# Transformer_FrontEnd_2.net
KiCad netlist of a schematic drawn in Altium Designer
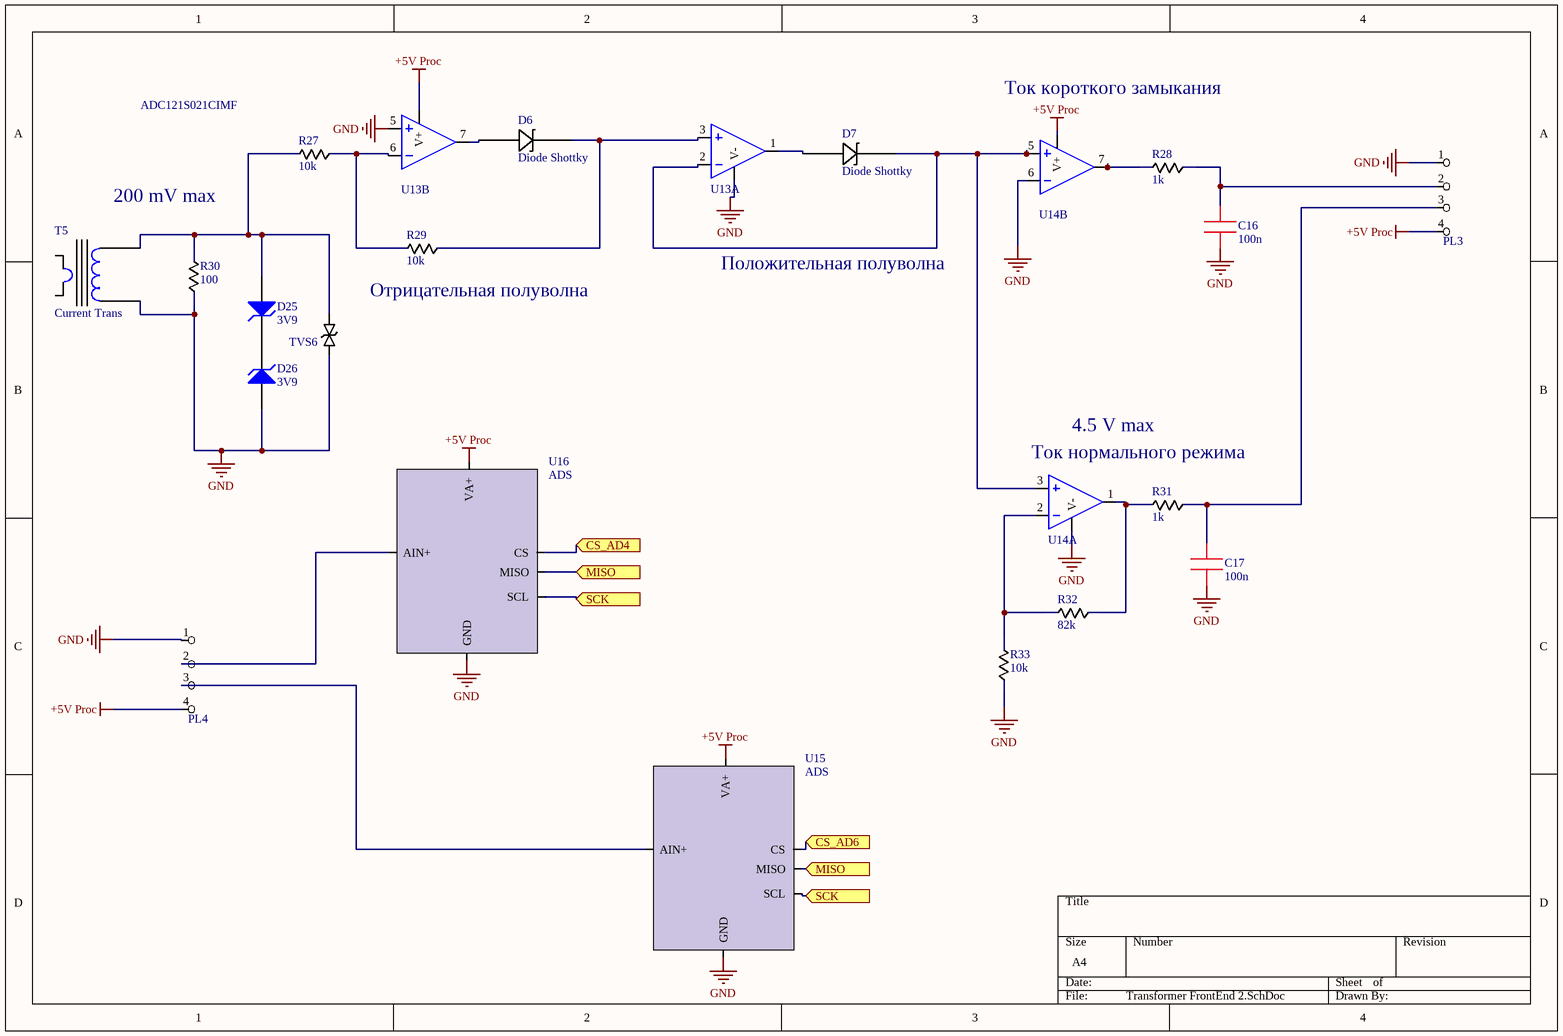
[diagram p0: Transformer FrontEnd 2.SchDoc]

(export (version "E")
  (design (tool "Eeschema 10.0.6"))
  (components
    (comp (ref "C16")
      (value "100n")
      (footprint "0603")
      (description "CC0603KRX7R9BB104")
      (libsource (lib "kontr") (part "0603 CAP"))
    )
    (comp (ref "C17")
      (value "100n")
      (footprint "0603")
      (description "CC0603KRX7R9BB104")
      (libsource (lib "kontr") (part "0603 CAP"))
    )
    (comp (ref "D6")
      (value "Diode Shottky")
      (footprint "SOD523")
      (description "RB751S40T1G")
      (libsource (lib "kontr") (part "Diode Shottky"))
    )
    (comp (ref "D7")
      (value "Diode Shottky")
      (footprint "SOD523")
      (description "RB751S40T1G")
      (libsource (lib "kontr") (part "Diode Shottky"))
    )
    (comp (ref "D25")
      (value "3V9")
      (footprint "PcbLib1:SOD80C")
      (description "BZV55-C3V9,115")
      (libsource (lib "Miscellaneous Devices") (part "D Zener"))
    )
    (comp (ref "D26")
      (value "3V9")
      (footprint "PcbLib1:SOD80C")
      (description "BZV55-C3V9,115")
      (libsource (lib "Miscellaneous Devices") (part "D Zener"))
    )
    (comp (ref "PL3")
      (value "plug")
      (footprint "PLS 4")
      (description "PLS-4R (DS1022-1x4R)")
      (libsource (lib "kontr") (part "PLS-4R"))
    )
    (comp (ref "PL4")
      (value "plug")
      (footprint "PLS 4")
      (description "PLS-4R (DS1022-1x4R)")
      (libsource (lib "kontr") (part "PLS-4R"))
    )
    (comp (ref "R27")
      (value "10k")
      (footprint "0603")
      (description "RT0603FRE0710KL")
      (libsource (lib "kontr") (part "0603 RES"))
    )
    (comp (ref "R28")
      (value "1k")
      (footprint "0603")
      (description "RC0603FR-071KL")
      (libsource (lib "kontr") (part "0603 RES"))
    )
    (comp (ref "R29")
      (value "10k")
      (footprint "0603")
      (description "RT0603FRE0710KL")
      (libsource (lib "kontr") (part "0603 RES"))
    )
    (comp (ref "R30")
      (value "100")
      (footprint "1206")
      (description "RT1206BRD07100RL")
      (libsource (lib "kontr") (part "SMD Resistor"))
    )
    (comp (ref "R31")
      (value "1k")
      (footprint "0603")
      (description "RC0603FR-071KL")
      (libsource (lib "kontr") (part "0603 RES"))
    )
    (comp (ref "R32")
      (value "82k")
      (footprint "0603")
      (description "ERJ3EKF8202V")
      (libsource (lib "kontr") (part "0603 RES"))
    )
    (comp (ref "R33")
      (value "10k")
      (footprint "0603")
      (description "RT0603FRE0710KL")
      (libsource (lib "kontr") (part "0603 RES"))
    )
    (comp (ref "T5")
      (value "Current Trans")
      (footprint "Talema")
      (description "AC-1005")
      (libsource (lib "kontr") (part "Current Trans"))
    )
    (comp (ref "TVS6")
      (value "SMAJ5.0CA")
      (footprint "DO-214AC")
      (libsource (lib "kontr") (part "SMAJ5.0CA"))
    )
    (comp (ref "U13")
      (value "OPAMP 2Ch")
      (footprint "SOIC 8")
      (description "TS272IDT")
      (libsource (lib "kontr") (part "OPAMP 2Ch"))
    )
    (comp (ref "U14")
      (value "OPAMP 2Ch")
      (footprint "SOIC 8")
      (description "TS272IDT")
      (libsource (lib "kontr") (part "OPAMP 2Ch"))
    )
    (comp (ref "U15")
      (value "ADS")
      (footprint "SOT23 - 6")
      (description "ADC121S021CIMF")
      (libsource (lib "kontr") (part "ADS"))
    )
    (comp (ref "U16")
      (value "ADS")
      (footprint "SOT23 - 6")
      (description "ADC121S021CIMF")
      (libsource (lib "kontr") (part "ADS"))
    )
  )
  (nets
    (net (code "1") (name "+5V Proc") (class "Default")
      (node (ref "PL3") (pin "4") (pinfunction "2_4") (pintype "passive"))
      (node (ref "PL4") (pin "4") (pinfunction "2_4") (pintype "passive"))
      (node (ref "U13") (pin "8") (pinfunction "V+_8") (pintype "passive"))
      (node (ref "U14") (pin "8") (pinfunction "V+_8") (pintype "passive"))
      (node (ref "U15") (pin "1") (pinfunction "VA+_1") (pintype "passive"))
      (node (ref "U16") (pin "1") (pinfunction "VA+_1") (pintype "passive"))
    )
    (net (code "2") (name "/CS_AD4") (class "Default")
      (node (ref "U16") (pin "6") (pinfunction "CS_6") (pintype "passive"))
    )
    (net (code "3") (name "/CS_AD6") (class "Default")
      (node (ref "U15") (pin "6") (pinfunction "CS_6") (pintype "passive"))
    )
    (net (code "4") (name "/MISO") (class "Default")
      (node (ref "U15") (pin "5") (pinfunction "MISO_5") (pintype "passive"))
      (node (ref "U16") (pin "5") (pinfunction "MISO_5") (pintype "passive"))
    )
    (net (code "5") (name "/SCK") (class "Default")
      (node (ref "U15") (pin "4") (pinfunction "SCL_4") (pintype "passive"))
      (node (ref "U16") (pin "4") (pinfunction "SCL_4") (pintype "passive"))
    )
    (net (code "6") (name "GND") (class "Default")
      (node (ref "C16") (pin "1") (pinfunction "1_1") (pintype "passive"))
      (node (ref "C17") (pin "1") (pinfunction "1_1") (pintype "passive"))
      (node (ref "D26") (pin "1") (pinfunction "A_1") (pintype "passive"))
      (node (ref "PL3") (pin "1") (pinfunction "1_1") (pintype "passive"))
      (node (ref "PL4") (pin "1") (pinfunction "1_1") (pintype "passive"))
      (node (ref "R30") (pin "1") (pintype "passive"))
      (node (ref "R33") (pin "1") (pintype "passive"))
      (node (ref "T5") (pin "2") (pinfunction "2_2") (pintype "passive"))
      (node (ref "TVS6") (pin "1") (pinfunction "1_1") (pintype "passive"))
      (node (ref "U13") (pin "4") (pinfunction "V-_4") (pintype "passive"))
      (node (ref "U13") (pin "5") (pinfunction "+IN_5") (pintype "passive"))
      (node (ref "U14") (pin "4") (pinfunction "V-_4") (pintype "passive"))
      (node (ref "U14") (pin "6") (pinfunction "-IN_6") (pintype "passive"))
      (node (ref "U15") (pin "2") (pinfunction "GND_2") (pintype "passive"))
      (node (ref "U16") (pin "2") (pinfunction "GND_2") (pintype "passive"))
    )
    (net (code "7") (name "Net-(C16-Pad2)") (class "Default")
      (node (ref "C16") (pin "2") (pinfunction "2_2") (pintype "passive"))
      (node (ref "PL3") (pin "2") (pinfunction "2_2") (pintype "passive"))
      (node (ref "R28") (pin "1") (pintype "passive"))
    )
    (net (code "8") (name "Net-(C17-Pad2)") (class "Default")
      (node (ref "C17") (pin "2") (pinfunction "2_2") (pintype "passive"))
      (node (ref "PL3") (pin "3") (pinfunction "1_3") (pintype "passive"))
      (node (ref "R31") (pin "1") (pintype "passive"))
    )
    (net (code "9") (name "Net-(D25-A)") (class "Default")
      (node (ref "D25") (pin "1") (pinfunction "A_1") (pintype "passive"))
      (node (ref "R27") (pin "2") (pintype "passive"))
      (node (ref "R30") (pin "2") (pintype "passive"))
      (node (ref "T5") (pin "1") (pinfunction "1_1") (pintype "passive"))
      (node (ref "TVS6") (pin "2") (pinfunction "2_2") (pintype "passive"))
    )
    (net (code "10") (name "Net-(D25-K)") (class "Default")
      (node (ref "D25") (pin "2") (pinfunction "K_2") (pintype "passive"))
      (node (ref "D26") (pin "2") (pinfunction "K_2") (pintype "passive"))
    )
    (net (code "11") (name "Net-(U13A-+IN)") (class "Default")
      (node (ref "D6") (pin "2") (pinfunction "2_2") (pintype "passive"))
      (node (ref "R29") (pin "1") (pintype "passive"))
      (node (ref "U13") (pin "3") (pinfunction "+IN_3") (pintype "passive"))
    )
    (net (code "12") (name "Net-(U13A--IN)") (class "Default")
      (node (ref "D7") (pin "2") (pinfunction "2_2") (pintype "passive"))
      (node (ref "U13") (pin "2") (pinfunction "-IN_2") (pintype "passive"))
      (node (ref "U14") (pin "3") (pinfunction "+IN_3") (pintype "passive"))
      (node (ref "U14") (pin "5") (pinfunction "+IN_5") (pintype "passive"))
    )
    (net (code "13") (name "Net-(U13A-OUT)") (class "Default")
      (node (ref "D7") (pin "1") (pinfunction "1_1") (pintype "passive"))
      (node (ref "U13") (pin "1") (pinfunction "OUT_1") (pintype "passive"))
    )
    (net (code "14") (name "Net-(U13B--IN)") (class "Default")
      (node (ref "R27") (pin "1") (pintype "passive"))
      (node (ref "R29") (pin "2") (pintype "passive"))
      (node (ref "U13") (pin "6") (pinfunction "-IN_6") (pintype "passive"))
    )
    (net (code "15") (name "Net-(U13B-OUT)") (class "Default")
      (node (ref "D6") (pin "1") (pinfunction "1_1") (pintype "passive"))
      (node (ref "U13") (pin "7") (pinfunction "OUT_7") (pintype "passive"))
    )
    (net (code "16") (name "Net-(U14A--IN)") (class "Default")
      (node (ref "R32") (pin "2") (pintype "passive"))
      (node (ref "R33") (pin "2") (pintype "passive"))
      (node (ref "U14") (pin "2") (pinfunction "-IN_2") (pintype "passive"))
    )
    (net (code "17") (name "Net-(U14A-OUT)") (class "Default")
      (node (ref "R31") (pin "2") (pintype "passive"))
      (node (ref "R32") (pin "1") (pintype "passive"))
      (node (ref "U14") (pin "1") (pinfunction "OUT_1") (pintype "passive"))
    )
    (net (code "18") (name "Net-(U14B-OUT)") (class "Default")
      (node (ref "R28") (pin "2") (pintype "passive"))
      (node (ref "U14") (pin "7") (pinfunction "OUT_7") (pintype "passive"))
    )
    (net (code "19") (name "Net-(U15-AIN+)") (class "Default")
      (node (ref "PL4") (pin "3") (pinfunction "1_3") (pintype "passive"))
      (node (ref "U15") (pin "3") (pinfunction "AIN+_3") (pintype "passive"))
    )
    (net (code "20") (name "Net-(U16-AIN+)") (class "Default")
      (node (ref "PL4") (pin "2") (pinfunction "2_2") (pintype "passive"))
      (node (ref "U16") (pin "3") (pinfunction "AIN+_3") (pintype "passive"))
    )
  )
)
